# hrm-shield.net
KiCad netlist of a schematic drawn in EAGLE
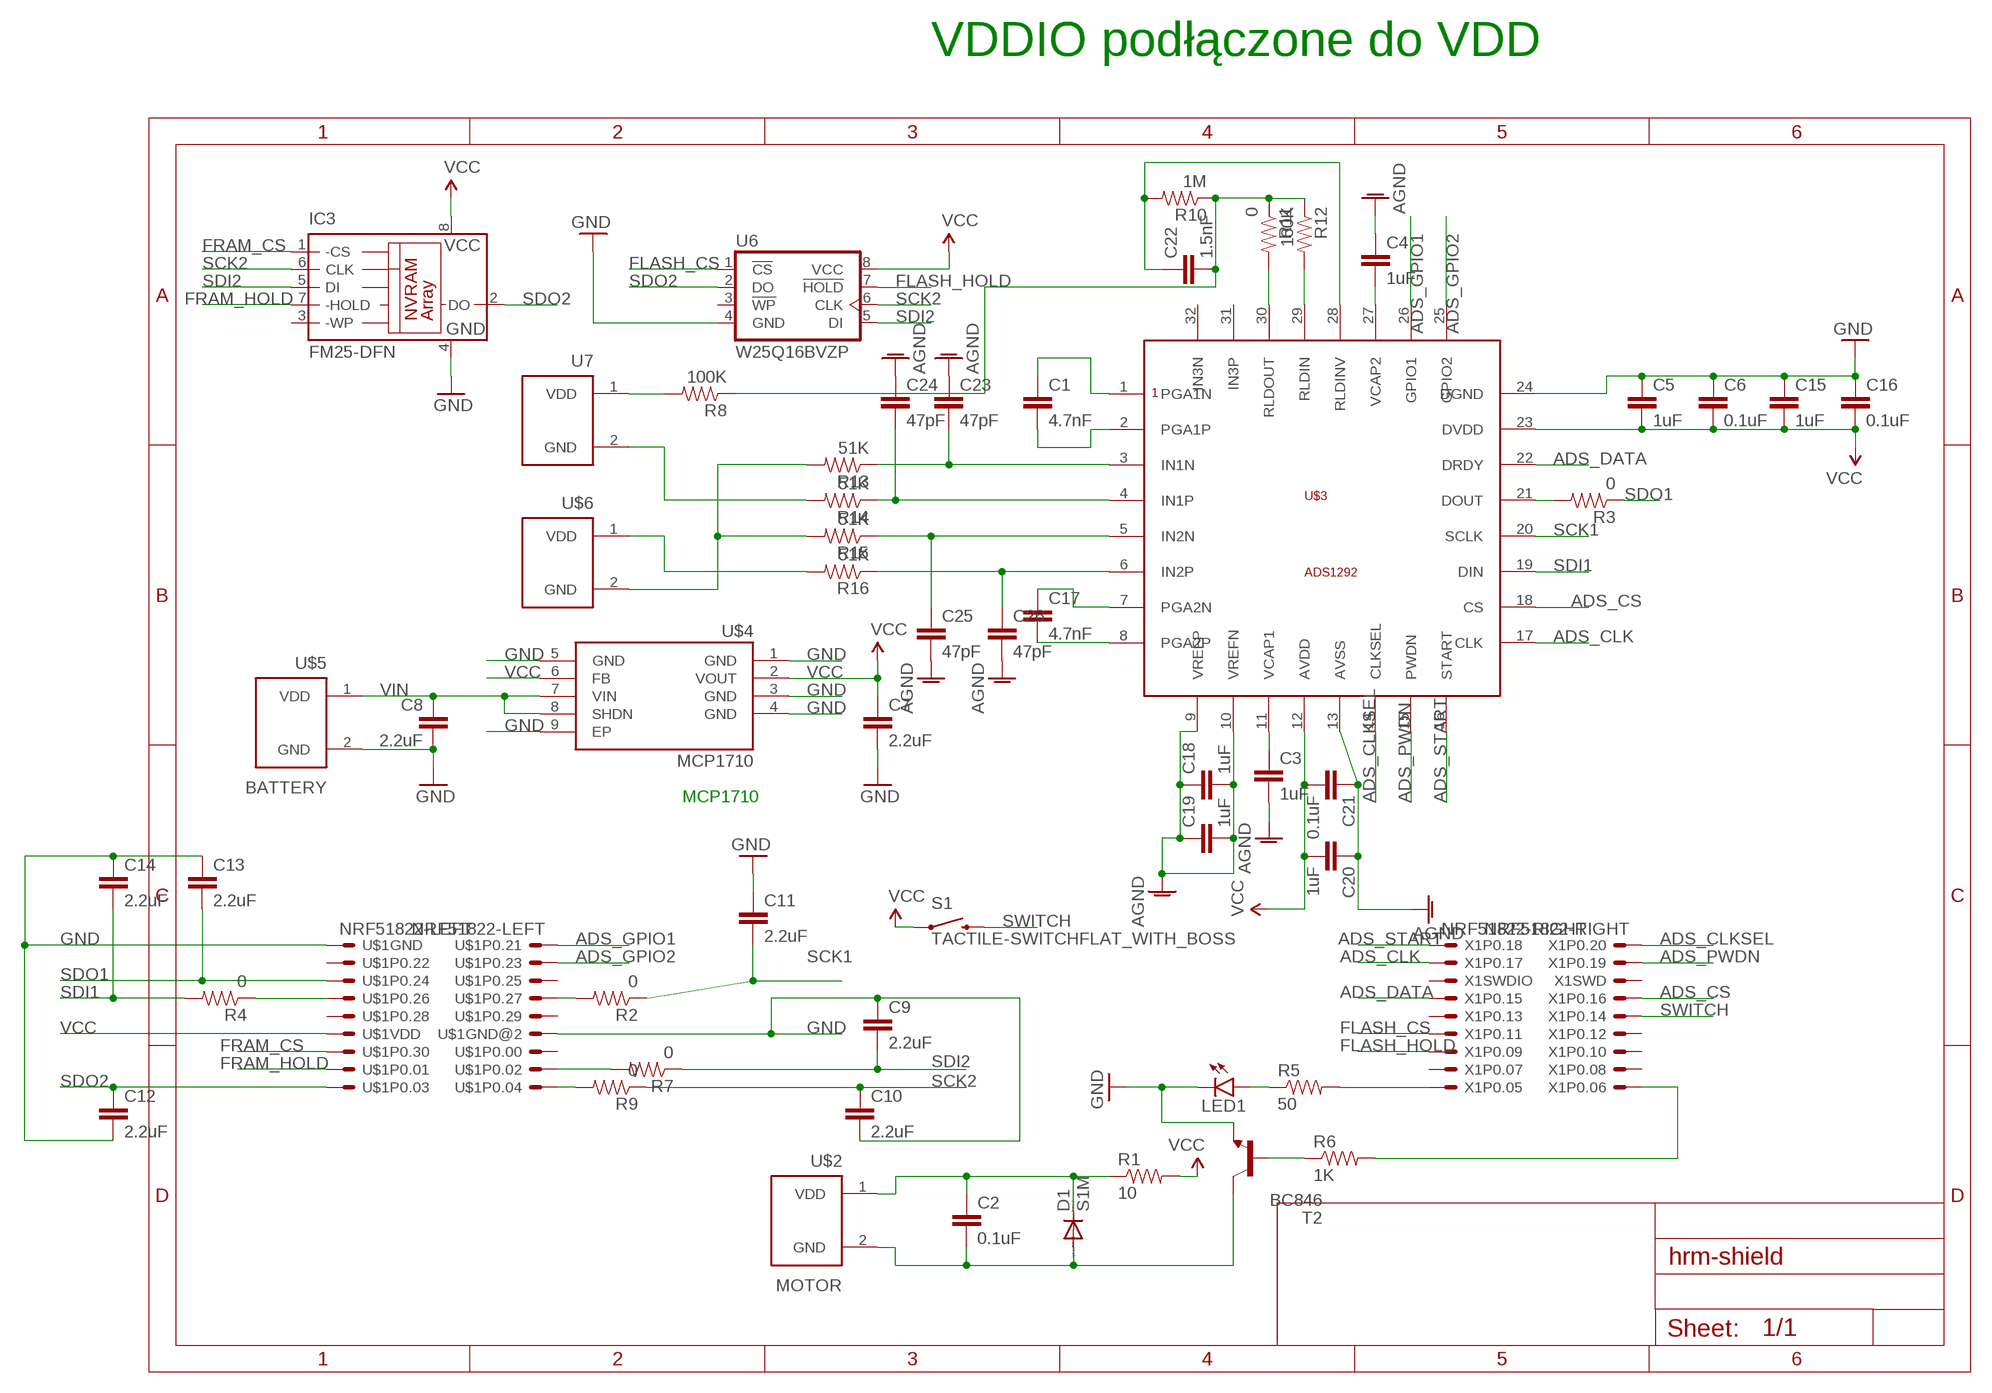
[diagram p0: schematic, sheet 1]

(export (version "E")
  (design (tool "Eeschema 10.0.6"))
  (components
    (comp (ref "C1")
      (value "4.7nF")
      (footprint "eagle-import:0603-CAP")
      (libsource (lib "eagle-import") (part "0.1UF-25V(+80/-20%)(0603)"))
    )
    (comp (ref "C2")
      (value "0.1uF")
      (footprint "eagle-import:0603-CAP")
      (libsource (lib "eagle-import") (part "0.1UF-25V(+80/-20%)(0603)"))
    )
    (comp (ref "C3")
      (value "1uF")
      (footprint "eagle-import:0603-CAP")
      (libsource (lib "eagle-import") (part "0.1UF-25V(+80/-20%)(0603)"))
    )
    (comp (ref "C4")
      (value "1uF")
      (footprint "eagle-import:0603-CAP")
      (libsource (lib "eagle-import") (part "0.1UF-25V(+80/-20%)(0603)"))
    )
    (comp (ref "C5")
      (value "1uF")
      (footprint "eagle-import:0603-CAP")
      (libsource (lib "eagle-import") (part "0.1UF-25V(+80/-20%)(0603)"))
    )
    (comp (ref "C6")
      (value "0.1uF")
      (footprint "eagle-import:0603-CAP")
      (libsource (lib "eagle-import") (part "0.1UF-25V(+80/-20%)(0603)"))
    )
    (comp (ref "C7")
      (value "2.2uF")
      (footprint "eagle-import:0603-CAP")
      (libsource (lib "eagle-import") (part "0.1UF-25V(+80/-20%)(0603)"))
    )
    (comp (ref "C8")
      (value "2.2uF")
      (footprint "eagle-import:0603-CAP")
      (libsource (lib "eagle-import") (part "0.1UF-25V(+80/-20%)(0603)"))
    )
    (comp (ref "C9")
      (value "2.2uF")
      (footprint "eagle-import:0603-CAP")
      (libsource (lib "eagle-import") (part "0.1UF-25V(+80/-20%)(0603)"))
    )
    (comp (ref "C10")
      (value "2.2uF")
      (footprint "eagle-import:0603-CAP")
      (libsource (lib "eagle-import") (part "0.1UF-25V(+80/-20%)(0603)"))
    )
    (comp (ref "C11")
      (value "2.2uF")
      (footprint "eagle-import:0603-CAP")
      (libsource (lib "eagle-import") (part "0.1UF-25V(+80/-20%)(0603)"))
    )
    (comp (ref "C12")
      (value "2.2uF")
      (footprint "eagle-import:0603-CAP")
      (libsource (lib "eagle-import") (part "0.1UF-25V(+80/-20%)(0603)"))
    )
    (comp (ref "C13")
      (value "2.2uF")
      (footprint "eagle-import:0603-CAP")
      (libsource (lib "eagle-import") (part "0.1UF-25V(+80/-20%)(0603)"))
    )
    (comp (ref "C14")
      (value "2.2uF")
      (footprint "eagle-import:0603-CAP")
      (libsource (lib "eagle-import") (part "0.1UF-25V(+80/-20%)(0603)"))
    )
    (comp (ref "C15")
      (value "1uF")
      (footprint "eagle-import:0603-CAP")
      (libsource (lib "eagle-import") (part "0.1UF-25V(+80/-20%)(0603)"))
    )
    (comp (ref "C16")
      (value "0.1uF")
      (footprint "eagle-import:0603-CAP")
      (libsource (lib "eagle-import") (part "0.1UF-25V(+80/-20%)(0603)"))
    )
    (comp (ref "C17")
      (value "4.7nF")
      (footprint "eagle-import:0603-CAP")
      (libsource (lib "eagle-import") (part "0.1UF-25V(+80/-20%)(0603)"))
    )
    (comp (ref "C18")
      (value "1uF")
      (footprint "eagle-import:0603-CAP")
      (libsource (lib "eagle-import") (part "0.1UF-25V(+80/-20%)(0603)"))
    )
    (comp (ref "C19")
      (value "1uF")
      (footprint "eagle-import:0603-CAP")
      (libsource (lib "eagle-import") (part "0.1UF-25V(+80/-20%)(0603)"))
    )
    (comp (ref "C20")
      (value "1uF")
      (footprint "eagle-import:0603-CAP")
      (libsource (lib "eagle-import") (part "0.1UF-25V(+80/-20%)(0603)"))
    )
    (comp (ref "C21")
      (value "0.1uF")
      (footprint "eagle-import:0603-CAP")
      (libsource (lib "eagle-import") (part "0.1UF-25V(+80/-20%)(0603)"))
    )
    (comp (ref "C22")
      (value "1.5nF")
      (footprint "eagle-import:0603-CAP")
      (libsource (lib "eagle-import") (part "0.1UF-25V(+80/-20%)(0603)"))
    )
    (comp (ref "C23")
      (value "47pF")
      (footprint "eagle-import:0603-CAP")
      (libsource (lib "eagle-import") (part "0.1UF-25V(+80/-20%)(0603)"))
    )
    (comp (ref "C24")
      (value "47pF")
      (footprint "eagle-import:0603-CAP")
      (libsource (lib "eagle-import") (part "0.1UF-25V(+80/-20%)(0603)"))
    )
    (comp (ref "C25")
      (value "47pF")
      (footprint "eagle-import:0603-CAP")
      (libsource (lib "eagle-import") (part "0.1UF-25V(+80/-20%)(0603)"))
    )
    (comp (ref "C26")
      (value "47pF")
      (footprint "eagle-import:0603-CAP")
      (libsource (lib "eagle-import") (part "0.1UF-25V(+80/-20%)(0603)"))
    )
    (comp (ref "D1")
      (value "S1M")
      (footprint "eagle-import:SMA")
      (libsource (lib "eagle-import") (part "S1M"))
    )
    (comp (ref "IC3")
      (value "FM25-DFN")
      (footprint "eagle-import:DFN-8")
      (libsource (lib "eagle-import") (part "FM25-DFN"))
    )
    (comp (ref "LED1")
      (value "LED0603")
      (footprint "eagle-import:LED-0603")
      (libsource (lib "eagle-import") (part "LED0603"))
    )
    (comp (ref "R1")
      (value "10")
      (footprint "eagle-import:0603-RES")
      (libsource (lib "eagle-import") (part "1KOHM1/10W1%(0603)"))
    )
    (comp (ref "R2")
      (value "0")
      (footprint "eagle-import:0603-RES")
      (libsource (lib "eagle-import") (part "100OHM1/10W1%(0603)"))
    )
    (comp (ref "R3")
      (value "0")
      (footprint "eagle-import:0603-RES")
      (libsource (lib "eagle-import") (part "100OHM1/10W1%(0603)"))
    )
    (comp (ref "R4")
      (value "0")
      (footprint "eagle-import:0603-RES")
      (libsource (lib "eagle-import") (part "100OHM1/10W1%(0603)"))
    )
    (comp (ref "R5")
      (value "50")
      (footprint "eagle-import:0603-RES")
      (libsource (lib "eagle-import") (part "100OHM1/10W1%(0603)"))
    )
    (comp (ref "R6")
      (value "1K")
      (footprint "eagle-import:0603-RES")
      (libsource (lib "eagle-import") (part "1KOHM1/10W1%(0603)"))
    )
    (comp (ref "R7")
      (value "0")
      (footprint "eagle-import:0603-RES")
      (libsource (lib "eagle-import") (part "100OHM1/10W1%(0603)"))
    )
    (comp (ref "R8")
      (value "100K")
      (footprint "eagle-import:0603-RES")
      (libsource (lib "eagle-import") (part "100OHM1/10W1%(0603)"))
    )
    (comp (ref "R9")
      (value "0")
      (footprint "eagle-import:0603-RES")
      (libsource (lib "eagle-import") (part "100OHM1/10W1%(0603)"))
    )
    (comp (ref "R10")
      (value "1M")
      (footprint "eagle-import:0603-RES")
      (libsource (lib "eagle-import") (part "100OHM1/10W1%(0603)"))
    )
    (comp (ref "R11")
      (value "0")
      (footprint "eagle-import:0603-RES")
      (libsource (lib "eagle-import") (part "100OHM1/10W1%(0603)"))
    )
    (comp (ref "R12")
      (value "100K")
      (footprint "eagle-import:0603-RES")
      (libsource (lib "eagle-import") (part "100OHM1/10W1%(0603)"))
    )
    (comp (ref "R13")
      (value "51K")
      (footprint "eagle-import:0603-RES")
      (libsource (lib "eagle-import") (part "100OHM1/10W1%(0603)"))
    )
    (comp (ref "R14")
      (value "51K")
      (footprint "eagle-import:0603-RES")
      (libsource (lib "eagle-import") (part "100OHM1/10W1%(0603)"))
    )
    (comp (ref "R15")
      (value "51K")
      (footprint "eagle-import:0603-RES")
      (libsource (lib "eagle-import") (part "100OHM1/10W1%(0603)"))
    )
    (comp (ref "R16")
      (value "51K")
      (footprint "eagle-import:0603-RES")
      (libsource (lib "eagle-import") (part "100OHM1/10W1%(0603)"))
    )
    (comp (ref "S1")
      (value "TACTILE-SWITCHFLAT_WITH_BOSS")
      (footprint "eagle-import:TACTILE-SWITCH-SMD")
      (libsource (lib "eagle-import") (part "TACTILE-SWITCHFLAT_WITH_BOSS"))
    )
    (comp (ref "T2")
      (value "BC846")
      (footprint "eagle-import:SOT23")
      (libsource (lib "eagle-import") (part "BC846"))
    )
    (comp (ref "U$1")
      (value "NRF51822-LEFT")
      (footprint "eagle-import:NRF51822-LEFT")
      (fields (field (name "MPN") "NRF51822-left"))
      (libsource (lib "eagle-import") (part "NRF51822-LEFT"))
    )
    (comp (ref "U$2")
      (value "MOTOR")
      (footprint "eagle-import:EM406-2PIN")
      (libsource (lib "eagle-import") (part "EM406-2PINFLAT"))
    )
    (comp (ref "U$3")
      (value "ADS1292")
      (footprint "eagle-import:QFN-32-4X4")
      (libsource (lib "eagle-import") (part "ADS1292"))
    )
    (comp (ref "U$4")
      (value "MCP1710")
      (footprint "eagle-import:MCP1710")
      (libsource (lib "eagle-import") (part "MCP1710"))
    )
    (comp (ref "U$5")
      (value "BATTERY")
      (footprint "eagle-import:EM406-2PIN")
      (libsource (lib "eagle-import") (part "EM406-2PINFLAT"))
    )
    (comp (ref "U$6")
      (value "EM406-2PINFLAT")
      (footprint "eagle-import:EM406-2PIN")
      (libsource (lib "eagle-import") (part "EM406-2PINFLAT"))
    )
    (comp (ref "U6")
      (value "W25Q16BVZP")
      (footprint "eagle-import:WSON8")
      (libsource (lib "eagle-import") (part "W25Q16BVZP"))
    )
    (comp (ref "U7")
      (value "EM406-2PINFLAT")
      (footprint "eagle-import:EM406-2PIN")
      (libsource (lib "eagle-import") (part "EM406-2PINFLAT"))
    )
    (comp (ref "X1")
      (value "NRF51822-RIGHT")
      (footprint "eagle-import:NRF51822-RIGHT")
      (fields (field (name "MPN") "NRF51822-right"))
      (libsource (lib "eagle-import") (part "NRF51822-RIGHT"))
    )
  )
  (nets
    (net (code "1") (name "/ADS_CLK") (class "Default")
      (node (ref "U$3") (pin "17") (pinfunction "CLK_17") (pintype "bidirectional"))
      (node (ref "X1") (pin "3") (pinfunction "S_3") (pintype "passive"))
    )
    (net (code "2") (name "/ADS_CLKSEL") (class "Default")
      (node (ref "U$3") (pin "14") (pinfunction "CLKSEL_14") (pintype "bidirectional"))
      (node (ref "X1") (pin "2") (pinfunction "S_2") (pintype "passive"))
    )
    (net (code "3") (name "/ADS_CS") (class "Default")
      (node (ref "U$3") (pin "18") (pinfunction "CS_18") (pintype "bidirectional"))
      (node (ref "X1") (pin "8") (pinfunction "S_8") (pintype "passive"))
    )
    (net (code "4") (name "/ADS_DATA") (class "Default")
      (node (ref "U$3") (pin "22") (pinfunction "DRDY_22") (pintype "bidirectional"))
      (node (ref "X1") (pin "7") (pinfunction "S_7") (pintype "passive"))
    )
    (net (code "5") (name "/ADS_GPIO1") (class "Default")
      (node (ref "U$1") (pin "2") (pinfunction "S_2") (pintype "passive"))
      (node (ref "U$3") (pin "26") (pinfunction "GPIO1_26") (pintype "bidirectional"))
    )
    (net (code "6") (name "/ADS_GPIO2") (class "Default")
      (node (ref "U$1") (pin "4") (pinfunction "S_4") (pintype "passive"))
      (node (ref "U$3") (pin "25") (pinfunction "GPIO2_25") (pintype "bidirectional"))
    )
    (net (code "7") (name "/ADS_PWDN") (class "Default")
      (node (ref "U$3") (pin "15") (pinfunction "PWDN_15") (pintype "bidirectional"))
      (node (ref "X1") (pin "4") (pinfunction "S_4") (pintype "passive"))
    )
    (net (code "8") (name "/ADS_START") (class "Default")
      (node (ref "U$3") (pin "16") (pinfunction "START_16") (pintype "bidirectional"))
      (node (ref "X1") (pin "1") (pinfunction "S_1") (pintype "passive"))
    )
    (net (code "9") (name "/FLASH_CS") (class "Default")
      (node (ref "U6") (pin "1") (pinfunction "~{CS}_1") (pintype "input"))
      (node (ref "X1") (pin "11") (pinfunction "S_11") (pintype "passive"))
    )
    (net (code "10") (name "/FLASH_HOLD") (class "Default")
      (node (ref "U6") (pin "7") (pinfunction "~{HOLD}_7") (pintype "input"))
      (node (ref "X1") (pin "13") (pinfunction "S_13") (pintype "passive"))
    )
    (net (code "11") (name "/FRAM_CS") (class "Default")
      (node (ref "IC3") (pin "1") (pinfunction "-CS_1") (pintype "input"))
      (node (ref "U$1") (pin "13") (pinfunction "S_13") (pintype "passive"))
    )
    (net (code "12") (name "/FRAM_HOLD") (class "Default")
      (node (ref "IC3") (pin "7") (pinfunction "-HOLD_7") (pintype "input"))
      (node (ref "U$1") (pin "15") (pinfunction "S_15") (pintype "passive"))
    )
    (net (code "13") (name "/SCK1") (class "Default")
      (node (ref "C11") (pin "2") (pinfunction "2_2") (pintype "passive"))
      (node (ref "R2") (pin "1") (pinfunction "1_1") (pintype "passive"))
      (node (ref "U$3") (pin "20") (pinfunction "SCLK_20") (pintype "bidirectional"))
    )
    (net (code "14") (name "/SCK2") (class "Default")
      (node (ref "C10") (pin "1") (pinfunction "1_1") (pintype "passive"))
      (node (ref "IC3") (pin "6") (pinfunction "CLK_6") (pintype "input"))
      (node (ref "R9") (pin "1") (pinfunction "1_1") (pintype "passive"))
      (node (ref "U6") (pin "6") (pinfunction "CLK_6") (pintype "input"))
    )
    (net (code "15") (name "/SDI1") (class "Default")
      (node (ref "C14") (pin "2") (pinfunction "2_2") (pintype "passive"))
      (node (ref "R4") (pin "2") (pinfunction "2_2") (pintype "passive"))
      (node (ref "U$3") (pin "19") (pinfunction "DIN_19") (pintype "bidirectional"))
    )
    (net (code "16") (name "/SDI2") (class "Default")
      (node (ref "C9") (pin "2") (pinfunction "2_2") (pintype "passive"))
      (node (ref "IC3") (pin "5") (pinfunction "DI_5") (pintype "input"))
      (node (ref "R7") (pin "1") (pinfunction "1_1") (pintype "passive"))
      (node (ref "U6") (pin "5") (pinfunction "DI_5") (pintype "input"))
    )
    (net (code "17") (name "/SDO1") (class "Default")
      (node (ref "C13") (pin "2") (pinfunction "2_2") (pintype "passive"))
      (node (ref "R3") (pin "1") (pinfunction "1_1") (pintype "passive"))
      (node (ref "U$1") (pin "5") (pinfunction "S_5") (pintype "passive"))
    )
    (net (code "18") (name "/SDO2") (class "Default")
      (node (ref "C12") (pin "1") (pinfunction "1_1") (pintype "passive"))
      (node (ref "IC3") (pin "2") (pinfunction "DO_2") (pintype "output"))
      (node (ref "U$1") (pin "17") (pinfunction "S_17") (pintype "passive"))
      (node (ref "U6") (pin "2") (pinfunction "DO_2") (pintype "output"))
    )
    (net (code "19") (name "/SWITCH") (class "Default")
      (node (ref "S1") (pin "2") (pinfunction "2_2") (pintype "passive"))
      (node (ref "X1") (pin "10") (pinfunction "S_10") (pintype "passive"))
    )
    (net (code "20") (name "/VIN") (class "Default")
      (node (ref "C8") (pin "1") (pinfunction "1_1") (pintype "passive"))
      (node (ref "U$4") (pin "7") (pinfunction "VIN_7") (pintype "bidirectional"))
      (node (ref "U$4") (pin "8") (pinfunction "SHDN_8") (pintype "bidirectional"))
      (node (ref "U$5") (pin "1") (pinfunction "VDD_1") (pintype "bidirectional"))
    )
    (net (code "21") (name "AGND") (class "Default")
      (node (ref "C18") (pin "1") (pinfunction "1_1") (pintype "passive"))
      (node (ref "C18") (pin "2") (pinfunction "2_2") (pintype "passive"))
      (node (ref "C19") (pin "1") (pinfunction "1_1") (pintype "passive"))
      (node (ref "C19") (pin "2") (pinfunction "2_2") (pintype "passive"))
      (node (ref "C20") (pin "1") (pinfunction "1_1") (pintype "passive"))
      (node (ref "C21") (pin "1") (pinfunction "1_1") (pintype "passive"))
      (node (ref "C23") (pin "1") (pinfunction "1_1") (pintype "passive"))
      (node (ref "C24") (pin "1") (pinfunction "1_1") (pintype "passive"))
      (node (ref "C25") (pin "2") (pinfunction "2_2") (pintype "passive"))
      (node (ref "C26") (pin "2") (pinfunction "2_2") (pintype "passive"))
      (node (ref "C3") (pin "2") (pinfunction "2_2") (pintype "passive"))
      (node (ref "C4") (pin "1") (pinfunction "1_1") (pintype "passive"))
      (node (ref "U$3") (pin "10") (pinfunction "VREFN_10") (pintype "bidirectional"))
      (node (ref "U$3") (pin "13") (pinfunction "AVSS_13") (pintype "bidirectional"))
      (node (ref "U$3") (pin "9") (pinfunction "VREFP_9") (pintype "bidirectional"))
    )
    (net (code "22") (name "GND") (class "Default")
      (node (ref "C10") (pin "2") (pinfunction "2_2") (pintype "passive"))
      (node (ref "C11") (pin "1") (pinfunction "1_1") (pintype "passive"))
      (node (ref "C12") (pin "2") (pinfunction "2_2") (pintype "passive"))
      (node (ref "C13") (pin "1") (pinfunction "1_1") (pintype "passive"))
      (node (ref "C14") (pin "1") (pinfunction "1_1") (pintype "passive"))
      (node (ref "C15") (pin "1") (pinfunction "1_1") (pintype "passive"))
      (node (ref "C16") (pin "1") (pinfunction "1_1") (pintype "passive"))
      (node (ref "C5") (pin "1") (pinfunction "1_1") (pintype "passive"))
      (node (ref "C6") (pin "1") (pinfunction "1_1") (pintype "passive"))
      (node (ref "C7") (pin "2") (pinfunction "2_2") (pintype "passive"))
      (node (ref "C8") (pin "2") (pinfunction "2_2") (pintype "passive"))
      (node (ref "C9") (pin "1") (pinfunction "1_1") (pintype "passive"))
      (node (ref "IC3") (pin "4") (pinfunction "GND_4") (pintype "power_in"))
      (node (ref "LED1") (pin "C") (pinfunction "C_C") (pintype "passive"))
      (node (ref "T2") (pin "2") (pinfunction "E_2") (pintype "passive"))
      (node (ref "U$1") (pin "1") (pinfunction "S_1") (pintype "passive"))
      (node (ref "U$1") (pin "12") (pinfunction "S_12") (pintype "passive"))
      (node (ref "U$3") (pin "24") (pinfunction "DGND_24") (pintype "bidirectional"))
      (node (ref "U$4") (pin "1") (pinfunction "GND_1") (pintype "bidirectional"))
      (node (ref "U$4") (pin "3") (pinfunction "GND_3") (pintype "bidirectional"))
      (node (ref "U$4") (pin "4") (pinfunction "GND_4") (pintype "bidirectional"))
      (node (ref "U$4") (pin "5") (pinfunction "GND_5") (pintype "bidirectional"))
      (node (ref "U$4") (pin "9") (pinfunction "EP_9") (pintype "bidirectional"))
      (node (ref "U$5") (pin "2") (pinfunction "GND_2") (pintype "bidirectional"))
      (node (ref "U6") (pin "4") (pinfunction "GND_4") (pintype "power_in"))
    )
    (net (code "23") (name "Net-(C22-Pad2)") (class "Default")
      (node (ref "C22") (pin "2") (pinfunction "2_2") (pintype "passive"))
      (node (ref "R10") (pin "1") (pinfunction "1_1") (pintype "passive"))
      (node (ref "R11") (pin "1") (pinfunction "1_1") (pintype "passive"))
      (node (ref "R12") (pin "1") (pinfunction "1_1") (pintype "passive"))
      (node (ref "R8") (pin "1") (pinfunction "1_1") (pintype "passive"))
    )
    (net (code "24") (name "Net-(LED1-PadA)") (class "Default")
      (node (ref "LED1") (pin "A") (pinfunction "A_A") (pintype "passive"))
      (node (ref "R5") (pin "1") (pinfunction "1_1") (pintype "passive"))
    )
    (net (code "25") (name "Net-(T2-B)") (class "Default")
      (node (ref "R6") (pin "1") (pinfunction "1_1") (pintype "passive"))
      (node (ref "T2") (pin "1") (pinfunction "B_1") (pintype "passive"))
    )
    (net (code "26") (name "Net-(T2-C)") (class "Default")
      (node (ref "C2") (pin "2") (pinfunction "2_2") (pintype "passive"))
      (node (ref "D1") (pin "A") (pinfunction "A_A") (pintype "passive"))
      (node (ref "T2") (pin "3") (pinfunction "C_3") (pintype "passive"))
      (node (ref "U$2") (pin "2") (pinfunction "GND_2") (pintype "bidirectional"))
    )
    (net (code "27") (name "Net-(U$1E-S)") (class "Default")
      (node (ref "R7") (pin "2") (pinfunction "2_2") (pintype "passive"))
      (node (ref "U$1") (pin "16") (pinfunction "S_16") (pintype "passive"))
    )
    (net (code "28") (name "Net-(U$1G-S)") (class "Default")
      (node (ref "R9") (pin "2") (pinfunction "2_2") (pintype "passive"))
      (node (ref "U$1") (pin "18") (pinfunction "S_18") (pintype "passive"))
    )
    (net (code "29") (name "Net-(U$1M-S)") (class "Default")
      (node (ref "R4") (pin "1") (pinfunction "1_1") (pintype "passive"))
      (node (ref "U$1") (pin "7") (pinfunction "S_7") (pintype "passive"))
    )
    (net (code "30") (name "Net-(U$1N-S)") (class "Default")
      (node (ref "R2") (pin "2") (pinfunction "2_2") (pintype "passive"))
      (node (ref "U$1") (pin "8") (pinfunction "S_8") (pintype "passive"))
    )
    (net (code "31") (name "Net-(U$2-VDD)") (class "Default")
      (node (ref "C2") (pin "1") (pinfunction "1_1") (pintype "passive"))
      (node (ref "D1") (pin "C") (pinfunction "C_C") (pintype "passive"))
      (node (ref "R1") (pin "1") (pinfunction "1_1") (pintype "passive"))
      (node (ref "U$2") (pin "1") (pinfunction "VDD_1") (pintype "bidirectional"))
    )
    (net (code "32") (name "Net-(U$3-DOUT)") (class "Default")
      (node (ref "R3") (pin "2") (pinfunction "2_2") (pintype "passive"))
      (node (ref "U$3") (pin "21") (pinfunction "DOUT_21") (pintype "bidirectional"))
    )
    (net (code "33") (name "Net-(U$3-IN1N)") (class "Default")
      (node (ref "C23") (pin "2") (pinfunction "2_2") (pintype "passive"))
      (node (ref "R13") (pin "1") (pinfunction "1_1") (pintype "passive"))
      (node (ref "U$3") (pin "3") (pinfunction "IN1N_3") (pintype "bidirectional"))
    )
    (net (code "34") (name "Net-(U$3-IN1P)") (class "Default")
      (node (ref "C24") (pin "2") (pinfunction "2_2") (pintype "passive"))
      (node (ref "R14") (pin "1") (pinfunction "1_1") (pintype "passive"))
      (node (ref "U$3") (pin "4") (pinfunction "IN1P_4") (pintype "bidirectional"))
    )
    (net (code "35") (name "Net-(U$3-IN2N)") (class "Default")
      (node (ref "C25") (pin "1") (pinfunction "1_1") (pintype "passive"))
      (node (ref "R15") (pin "1") (pinfunction "1_1") (pintype "passive"))
      (node (ref "U$3") (pin "5") (pinfunction "IN2N_5") (pintype "bidirectional"))
    )
    (net (code "36") (name "Net-(U$3-IN2P)") (class "Default")
      (node (ref "C26") (pin "1") (pinfunction "1_1") (pintype "passive"))
      (node (ref "R16") (pin "1") (pinfunction "1_1") (pintype "passive"))
      (node (ref "U$3") (pin "6") (pinfunction "IN2P_6") (pintype "bidirectional"))
    )
    (net (code "37") (name "Net-(U$3-PGA1N)") (class "Default")
      (node (ref "C1") (pin "1") (pinfunction "1_1") (pintype "passive"))
      (node (ref "U$3") (pin "1") (pinfunction "PGA1N_1") (pintype "bidirectional"))
    )
    (net (code "38") (name "Net-(U$3-PGA1P)") (class "Default")
      (node (ref "C1") (pin "2") (pinfunction "2_2") (pintype "passive"))
      (node (ref "U$3") (pin "2") (pinfunction "PGA1P_2") (pintype "bidirectional"))
    )
    (net (code "39") (name "Net-(U$3-PGA2N)") (class "Default")
      (node (ref "C17") (pin "1") (pinfunction "1_1") (pintype "passive"))
      (node (ref "U$3") (pin "7") (pinfunction "PGA2N_7") (pintype "bidirectional"))
    )
    (net (code "40") (name "Net-(U$3-PGA2P)") (class "Default")
      (node (ref "C17") (pin "2") (pinfunction "2_2") (pintype "passive"))
      (node (ref "U$3") (pin "8") (pinfunction "PGA2P_8") (pintype "bidirectional"))
    )
    (net (code "41") (name "Net-(U$3-RLDIN)") (class "Default")
      (node (ref "R12") (pin "2") (pinfunction "2_2") (pintype "passive"))
      (node (ref "U$3") (pin "29") (pinfunction "RLDIN_29") (pintype "bidirectional"))
    )
    (net (code "42") (name "Net-(U$3-RLDINV)") (class "Default")
      (node (ref "C22") (pin "1") (pinfunction "1_1") (pintype "passive"))
      (node (ref "R10") (pin "2") (pinfunction "2_2") (pintype "passive"))
      (node (ref "U$3") (pin "28") (pinfunction "RLDINV_28") (pintype "bidirectional"))
    )
    (net (code "43") (name "Net-(U$3-RLDOUT)") (class "Default")
      (node (ref "R11") (pin "2") (pinfunction "2_2") (pintype "passive"))
      (node (ref "U$3") (pin "30") (pinfunction "RLDOUT_30") (pintype "bidirectional"))
    )
    (net (code "44") (name "Net-(U$3-VCAP1)") (class "Default")
      (node (ref "C3") (pin "1") (pinfunction "1_1") (pintype "passive"))
      (node (ref "U$3") (pin "11") (pinfunction "VCAP1_11") (pintype "bidirectional"))
    )
    (net (code "45") (name "Net-(U$3-VCAP2)") (class "Default")
      (node (ref "C4") (pin "2") (pinfunction "2_2") (pintype "passive"))
      (node (ref "U$3") (pin "27") (pinfunction "VCAP2_27") (pintype "bidirectional"))
    )
    (net (code "46") (name "Net-(U$6-GND)") (class "Default")
      (node (ref "R13") (pin "2") (pinfunction "2_2") (pintype "passive"))
      (node (ref "R15") (pin "2") (pinfunction "2_2") (pintype "passive"))
      (node (ref "U$6") (pin "2") (pinfunction "GND_2") (pintype "bidirectional"))
    )
    (net (code "47") (name "Net-(U$6-VDD)") (class "Default")
      (node (ref "R16") (pin "2") (pinfunction "2_2") (pintype "passive"))
      (node (ref "U$6") (pin "1") (pinfunction "VDD_1") (pintype "bidirectional"))
    )
    (net (code "48") (name "Net-(U7-GND)") (class "Default")
      (node (ref "R14") (pin "2") (pinfunction "2_2") (pintype "passive"))
      (node (ref "U7") (pin "2") (pinfunction "GND_2") (pintype "bidirectional"))
    )
    (net (code "49") (name "Net-(U7-VDD)") (class "Default")
      (node (ref "R8") (pin "2") (pinfunction "2_2") (pintype "passive"))
      (node (ref "U7") (pin "1") (pinfunction "VDD_1") (pintype "bidirectional"))
    )
    (net (code "50") (name "Net-(X1A-S)") (class "Default")
      (node (ref "R5") (pin "2") (pinfunction "2_2") (pintype "passive"))
      (node (ref "X1") (pin "17") (pinfunction "S_17") (pintype "passive"))
    )
    (net (code "51") (name "Net-(X1B-S)") (class "Default")
      (node (ref "R6") (pin "2") (pinfunction "2_2") (pintype "passive"))
      (node (ref "X1") (pin "18") (pinfunction "S_18") (pintype "passive"))
    )
    (net (code "52") (name "VCC") (class "Default")
      (node (ref "C15") (pin "2") (pinfunction "2_2") (pintype "passive"))
      (node (ref "C16") (pin "2") (pinfunction "2_2") (pintype "passive"))
      (node (ref "C20") (pin "2") (pinfunction "2_2") (pintype "passive"))
      (node (ref "C21") (pin "2") (pinfunction "2_2") (pintype "passive"))
      (node (ref "C5") (pin "2") (pinfunction "2_2") (pintype "passive"))
      (node (ref "C6") (pin "2") (pinfunction "2_2") (pintype "passive"))
      (node (ref "C7") (pin "1") (pinfunction "1_1") (pintype "passive"))
      (node (ref "IC3") (pin "8") (pinfunction "VCC_8") (pintype "power_in"))
      (node (ref "R1") (pin "2") (pinfunction "2_2") (pintype "passive"))
      (node (ref "S1") (pin "1") (pinfunction "1_1") (pintype "passive"))
      (node (ref "U$1") (pin "11") (pinfunction "S_11") (pintype "passive"))
      (node (ref "U$3") (pin "12") (pinfunction "AVDD_12") (pintype "bidirectional"))
      (node (ref "U$3") (pin "23") (pinfunction "DVDD_23") (pintype "bidirectional"))
      (node (ref "U$4") (pin "2") (pinfunction "VOUT_2") (pintype "bidirectional"))
      (node (ref "U$4") (pin "6") (pinfunction "FB_6") (pintype "bidirectional"))
      (node (ref "U6") (pin "8") (pinfunction "VCC_8") (pintype "power_in"))
    )
    (net (code "53") (name "unconnected-(IC3--WP-Pad3)") (class "Default")
      (node (ref "IC3") (pin "3") (pinfunction "-WP_3") (pintype "input"))
    )
    (net (code "54") (name "unconnected-(U$1C-S-Pad14)") (class "Default")
      (node (ref "U$1") (pin "14") (pinfunction "S_14") (pintype "passive"))
    )
    (net (code "55") (name "unconnected-(U$1I-S-Pad3)") (class "Default")
      (node (ref "U$1") (pin "3") (pinfunction "S_3") (pintype "passive"))
    )
    (net (code "56") (name "unconnected-(U$1L-S-Pad6)") (class "Default")
      (node (ref "U$1") (pin "6") (pinfunction "S_6") (pintype "passive"))
    )
    (net (code "57") (name "unconnected-(U$1O-S-Pad9)") (class "Default")
      (node (ref "U$1") (pin "9") (pinfunction "S_9") (pintype "passive"))
    )
    (net (code "58") (name "unconnected-(U$1P-S-Pad10)") (class "Default")
      (node (ref "U$1") (pin "10") (pinfunction "S_10") (pintype "passive"))
    )
    (net (code "59") (name "unconnected-(U$3-IN3N-Pad32)") (class "Default")
      (node (ref "U$3") (pin "32") (pinfunction "IN3N_32") (pintype "bidirectional"))
    )
    (net (code "60") (name "unconnected-(U$3-IN3P-Pad31)") (class "Default")
      (node (ref "U$3") (pin "31") (pinfunction "IN3P_31") (pintype "bidirectional"))
    )
    (net (code "61") (name "unconnected-(U6-~{WP}-Pad3)") (class "Default")
      (node (ref "U6") (pin "3") (pinfunction "~{WP}_3") (pintype "input"))
    )
    (net (code "62") (name "unconnected-(X1C-S-Pad15)") (class "Default")
      (node (ref "X1") (pin "15") (pinfunction "S_15") (pintype "passive"))
    )
    (net (code "63") (name "unconnected-(X1D-S-Pad16)") (class "Default")
      (node (ref "X1") (pin "16") (pinfunction "S_16") (pintype "passive"))
    )
    (net (code "64") (name "unconnected-(X1F-S-Pad14)") (class "Default")
      (node (ref "X1") (pin "14") (pinfunction "S_14") (pintype "passive"))
    )
    (net (code "65") (name "unconnected-(X1H-S-Pad12)") (class "Default")
      (node (ref "X1") (pin "12") (pinfunction "S_12") (pintype "passive"))
    )
    (net (code "66") (name "unconnected-(X1I-S-Pad9)") (class "Default")
      (node (ref "X1") (pin "9") (pinfunction "S_9") (pintype "passive"))
    )
    (net (code "67") (name "unconnected-(X1Q-S-Pad6)") (class "Default")
      (node (ref "X1") (pin "6") (pinfunction "S_6") (pintype "passive"))
    )
    (net (code "68") (name "unconnected-(X1R-S-Pad5)") (class "Default")
      (node (ref "X1") (pin "5") (pinfunction "S_5") (pintype "passive"))
    )
  )
)
